# tlc5916-2seg.net
KiCad netlist of a schematic drawn in EAGLE
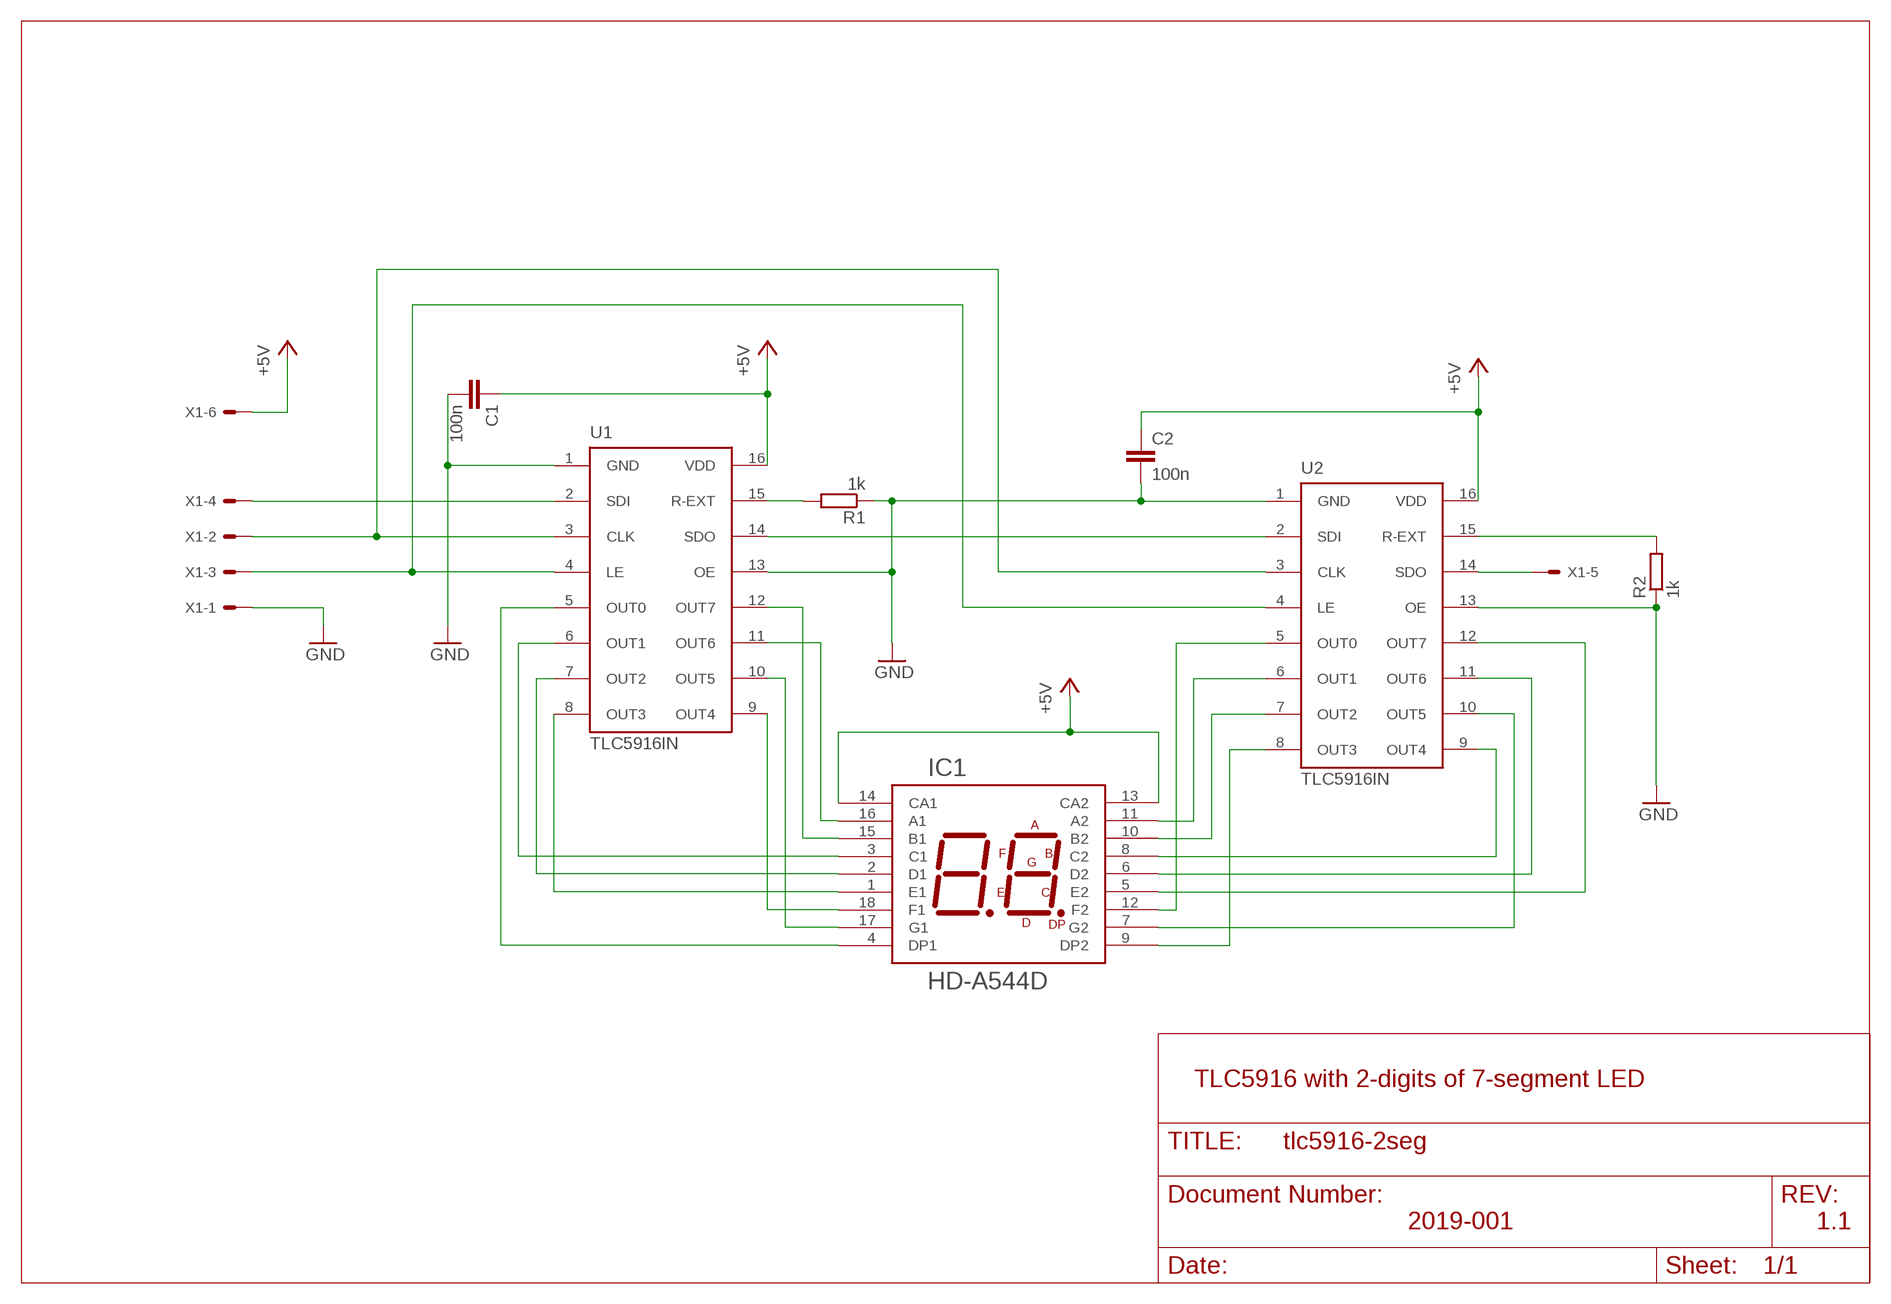
[diagram p0: schematic, sheet 1]

(export (version "E")
  (design (tool "Eeschema 10.0.6"))
  (components
    (comp (ref "C1")
      (value "100n")
      (footprint "eagle-import:C5B3")
      (libsource (lib "eagle-import") (part "C5/3"))
    )
    (comp (ref "C2")
      (value "100n")
      (footprint "eagle-import:C5B3")
      (libsource (lib "eagle-import") (part "C5/3"))
    )
    (comp (ref "IC1")
      (value "HD-A544D")
      (footprint "eagle-import:DIL18-SE")
      (libsource (lib "eagle-import") (part "HD-A544D"))
    )
    (comp (ref "R1")
      (value "1k")
      (footprint "eagle-import:0207_10")
      (libsource (lib "eagle-import") (part "R-EU_0207/10"))
    )
    (comp (ref "R2")
      (value "1k")
      (footprint "eagle-import:0207_10")
      (libsource (lib "eagle-import") (part "R-EU_0207/10"))
    )
    (comp (ref "U1")
      (value "TLC5916IN")
      (footprint "eagle-import:DIL16")
      (libsource (lib "eagle-import") (part "TLC5916IN"))
    )
    (comp (ref "U2")
      (value "TLC5916IN")
      (footprint "eagle-import:DIL16")
      (libsource (lib "eagle-import") (part "TLC5916IN"))
    )
    (comp (ref "X1")
      (value "22-23-2061")
      (footprint "eagle-import:22-23-2061")
      (fields (field (name "MF") "MOLEX"))
      (libsource (lib "eagle-import") (part "22-23-2061"))
    )
  )
  (nets
    (net (code "1") (name "+5V") (class "Default")
      (node (ref "C1") (pin "1") (pinfunction "1_1") (pintype "passive"))
      (node (ref "C2") (pin "1") (pinfunction "1_1") (pintype "passive"))
      (node (ref "IC1") (pin "13") (pinfunction "CA2_13") (pintype "bidirectional"))
      (node (ref "IC1") (pin "14") (pinfunction "CA1_14") (pintype "bidirectional"))
      (node (ref "U1") (pin "16") (pinfunction "VDD_16") (pintype "power_in"))
      (node (ref "U2") (pin "16") (pinfunction "VDD_16") (pintype "power_in"))
      (node (ref "X1") (pin "6") (pinfunction "S_6") (pintype "passive"))
    )
    (net (code "2") (name "GND") (class "Default")
      (node (ref "C1") (pin "2") (pinfunction "2_2") (pintype "passive"))
      (node (ref "C2") (pin "2") (pinfunction "2_2") (pintype "passive"))
      (node (ref "R1") (pin "1") (pinfunction "1_1") (pintype "passive"))
      (node (ref "R2") (pin "1") (pinfunction "1_1") (pintype "passive"))
      (node (ref "U1") (pin "1") (pinfunction "GND_1") (pintype "power_in"))
      (node (ref "U1") (pin "13") (pinfunction "OE_13") (pintype "input"))
      (node (ref "U2") (pin "1") (pinfunction "GND_1") (pintype "power_in"))
      (node (ref "U2") (pin "13") (pinfunction "OE_13") (pintype "input"))
      (node (ref "X1") (pin "1") (pinfunction "S_1") (pintype "passive"))
    )
    (net (code "3") (name "Net-(IC1-A1)") (class "Default")
      (node (ref "IC1") (pin "16") (pinfunction "A1_16") (pintype "bidirectional"))
      (node (ref "U1") (pin "11") (pinfunction "OUT6_11") (pintype "output"))
    )
    (net (code "4") (name "Net-(IC1-A2)") (class "Default")
      (node (ref "IC1") (pin "11") (pinfunction "A2_11") (pintype "bidirectional"))
      (node (ref "U2") (pin "6") (pinfunction "OUT1_6") (pintype "output"))
    )
    (net (code "5") (name "Net-(IC1-B1)") (class "Default")
      (node (ref "IC1") (pin "15") (pinfunction "B1_15") (pintype "bidirectional"))
      (node (ref "U1") (pin "12") (pinfunction "OUT7_12") (pintype "output"))
    )
    (net (code "6") (name "Net-(IC1-B2)") (class "Default")
      (node (ref "IC1") (pin "10") (pinfunction "B2_10") (pintype "bidirectional"))
      (node (ref "U2") (pin "7") (pinfunction "OUT2_7") (pintype "output"))
    )
    (net (code "7") (name "Net-(IC1-C1)") (class "Default")
      (node (ref "IC1") (pin "3") (pinfunction "C1_3") (pintype "bidirectional"))
      (node (ref "U1") (pin "6") (pinfunction "OUT1_6") (pintype "output"))
    )
    (net (code "8") (name "Net-(IC1-C2)") (class "Default")
      (node (ref "IC1") (pin "8") (pinfunction "C2_8") (pintype "bidirectional"))
      (node (ref "U2") (pin "9") (pinfunction "OUT4_9") (pintype "output"))
    )
    (net (code "9") (name "Net-(IC1-D1)") (class "Default")
      (node (ref "IC1") (pin "2") (pinfunction "D1_2") (pintype "bidirectional"))
      (node (ref "U1") (pin "7") (pinfunction "OUT2_7") (pintype "output"))
    )
    (net (code "10") (name "Net-(IC1-D2)") (class "Default")
      (node (ref "IC1") (pin "6") (pinfunction "D2_6") (pintype "bidirectional"))
      (node (ref "U2") (pin "11") (pinfunction "OUT6_11") (pintype "output"))
    )
    (net (code "11") (name "Net-(IC1-DP1)") (class "Default")
      (node (ref "IC1") (pin "4") (pinfunction "DP1_4") (pintype "bidirectional"))
      (node (ref "U1") (pin "5") (pinfunction "OUT0_5") (pintype "output"))
    )
    (net (code "12") (name "Net-(IC1-DP2)") (class "Default")
      (node (ref "IC1") (pin "9") (pinfunction "DP2_9") (pintype "bidirectional"))
      (node (ref "U2") (pin "8") (pinfunction "OUT3_8") (pintype "output"))
    )
    (net (code "13") (name "Net-(IC1-E1)") (class "Default")
      (node (ref "IC1") (pin "1") (pinfunction "E1_1") (pintype "bidirectional"))
      (node (ref "U1") (pin "8") (pinfunction "OUT3_8") (pintype "output"))
    )
    (net (code "14") (name "Net-(IC1-E2)") (class "Default")
      (node (ref "IC1") (pin "5") (pinfunction "E2_5") (pintype "bidirectional"))
      (node (ref "U2") (pin "12") (pinfunction "OUT7_12") (pintype "output"))
    )
    (net (code "15") (name "Net-(IC1-F1)") (class "Default")
      (node (ref "IC1") (pin "18") (pinfunction "F1_18") (pintype "bidirectional"))
      (node (ref "U1") (pin "9") (pinfunction "OUT4_9") (pintype "output"))
    )
    (net (code "16") (name "Net-(IC1-F2)") (class "Default")
      (node (ref "IC1") (pin "12") (pinfunction "F2_12") (pintype "bidirectional"))
      (node (ref "U2") (pin "5") (pinfunction "OUT0_5") (pintype "output"))
    )
    (net (code "17") (name "Net-(IC1-G1)") (class "Default")
      (node (ref "IC1") (pin "17") (pinfunction "G1_17") (pintype "bidirectional"))
      (node (ref "U1") (pin "10") (pinfunction "OUT5_10") (pintype "output"))
    )
    (net (code "18") (name "Net-(IC1-G2)") (class "Default")
      (node (ref "IC1") (pin "7") (pinfunction "G2_7") (pintype "bidirectional"))
      (node (ref "U2") (pin "10") (pinfunction "OUT5_10") (pintype "output"))
    )
    (net (code "19") (name "Net-(U1-CLK)") (class "Default")
      (node (ref "U1") (pin "3") (pinfunction "CLK_3") (pintype "input"))
      (node (ref "U2") (pin "3") (pinfunction "CLK_3") (pintype "input"))
      (node (ref "X1") (pin "2") (pinfunction "S_2") (pintype "passive"))
    )
    (net (code "20") (name "Net-(U1-LE)") (class "Default")
      (node (ref "U1") (pin "4") (pinfunction "LE_4") (pintype "input"))
      (node (ref "U2") (pin "4") (pinfunction "LE_4") (pintype "input"))
      (node (ref "X1") (pin "3") (pinfunction "S_3") (pintype "passive"))
    )
    (net (code "21") (name "Net-(U1-R-EXT)") (class "Default")
      (node (ref "R1") (pin "2") (pinfunction "2_2") (pintype "passive"))
      (node (ref "U1") (pin "15") (pinfunction "R-EXT_15") (pintype "input"))
    )
    (net (code "22") (name "Net-(U1-SDI)") (class "Default")
      (node (ref "U1") (pin "2") (pinfunction "SDI_2") (pintype "input"))
      (node (ref "X1") (pin "4") (pinfunction "S_4") (pintype "passive"))
    )
    (net (code "23") (name "Net-(U1-SDO)") (class "Default")
      (node (ref "U1") (pin "14") (pinfunction "SDO_14") (pintype "output"))
      (node (ref "U2") (pin "2") (pinfunction "SDI_2") (pintype "input"))
    )
    (net (code "24") (name "Net-(U2-R-EXT)") (class "Default")
      (node (ref "R2") (pin "2") (pinfunction "2_2") (pintype "passive"))
      (node (ref "U2") (pin "15") (pinfunction "R-EXT_15") (pintype "input"))
    )
    (net (code "25") (name "Net-(U2-SDO)") (class "Default")
      (node (ref "U2") (pin "14") (pinfunction "SDO_14") (pintype "output"))
      (node (ref "X1") (pin "5") (pinfunction "S_5") (pintype "passive"))
    )
  )
)
